# PowerInjectionControlBoardV4.net
KiCad netlist of a schematic drawn in EAGLE
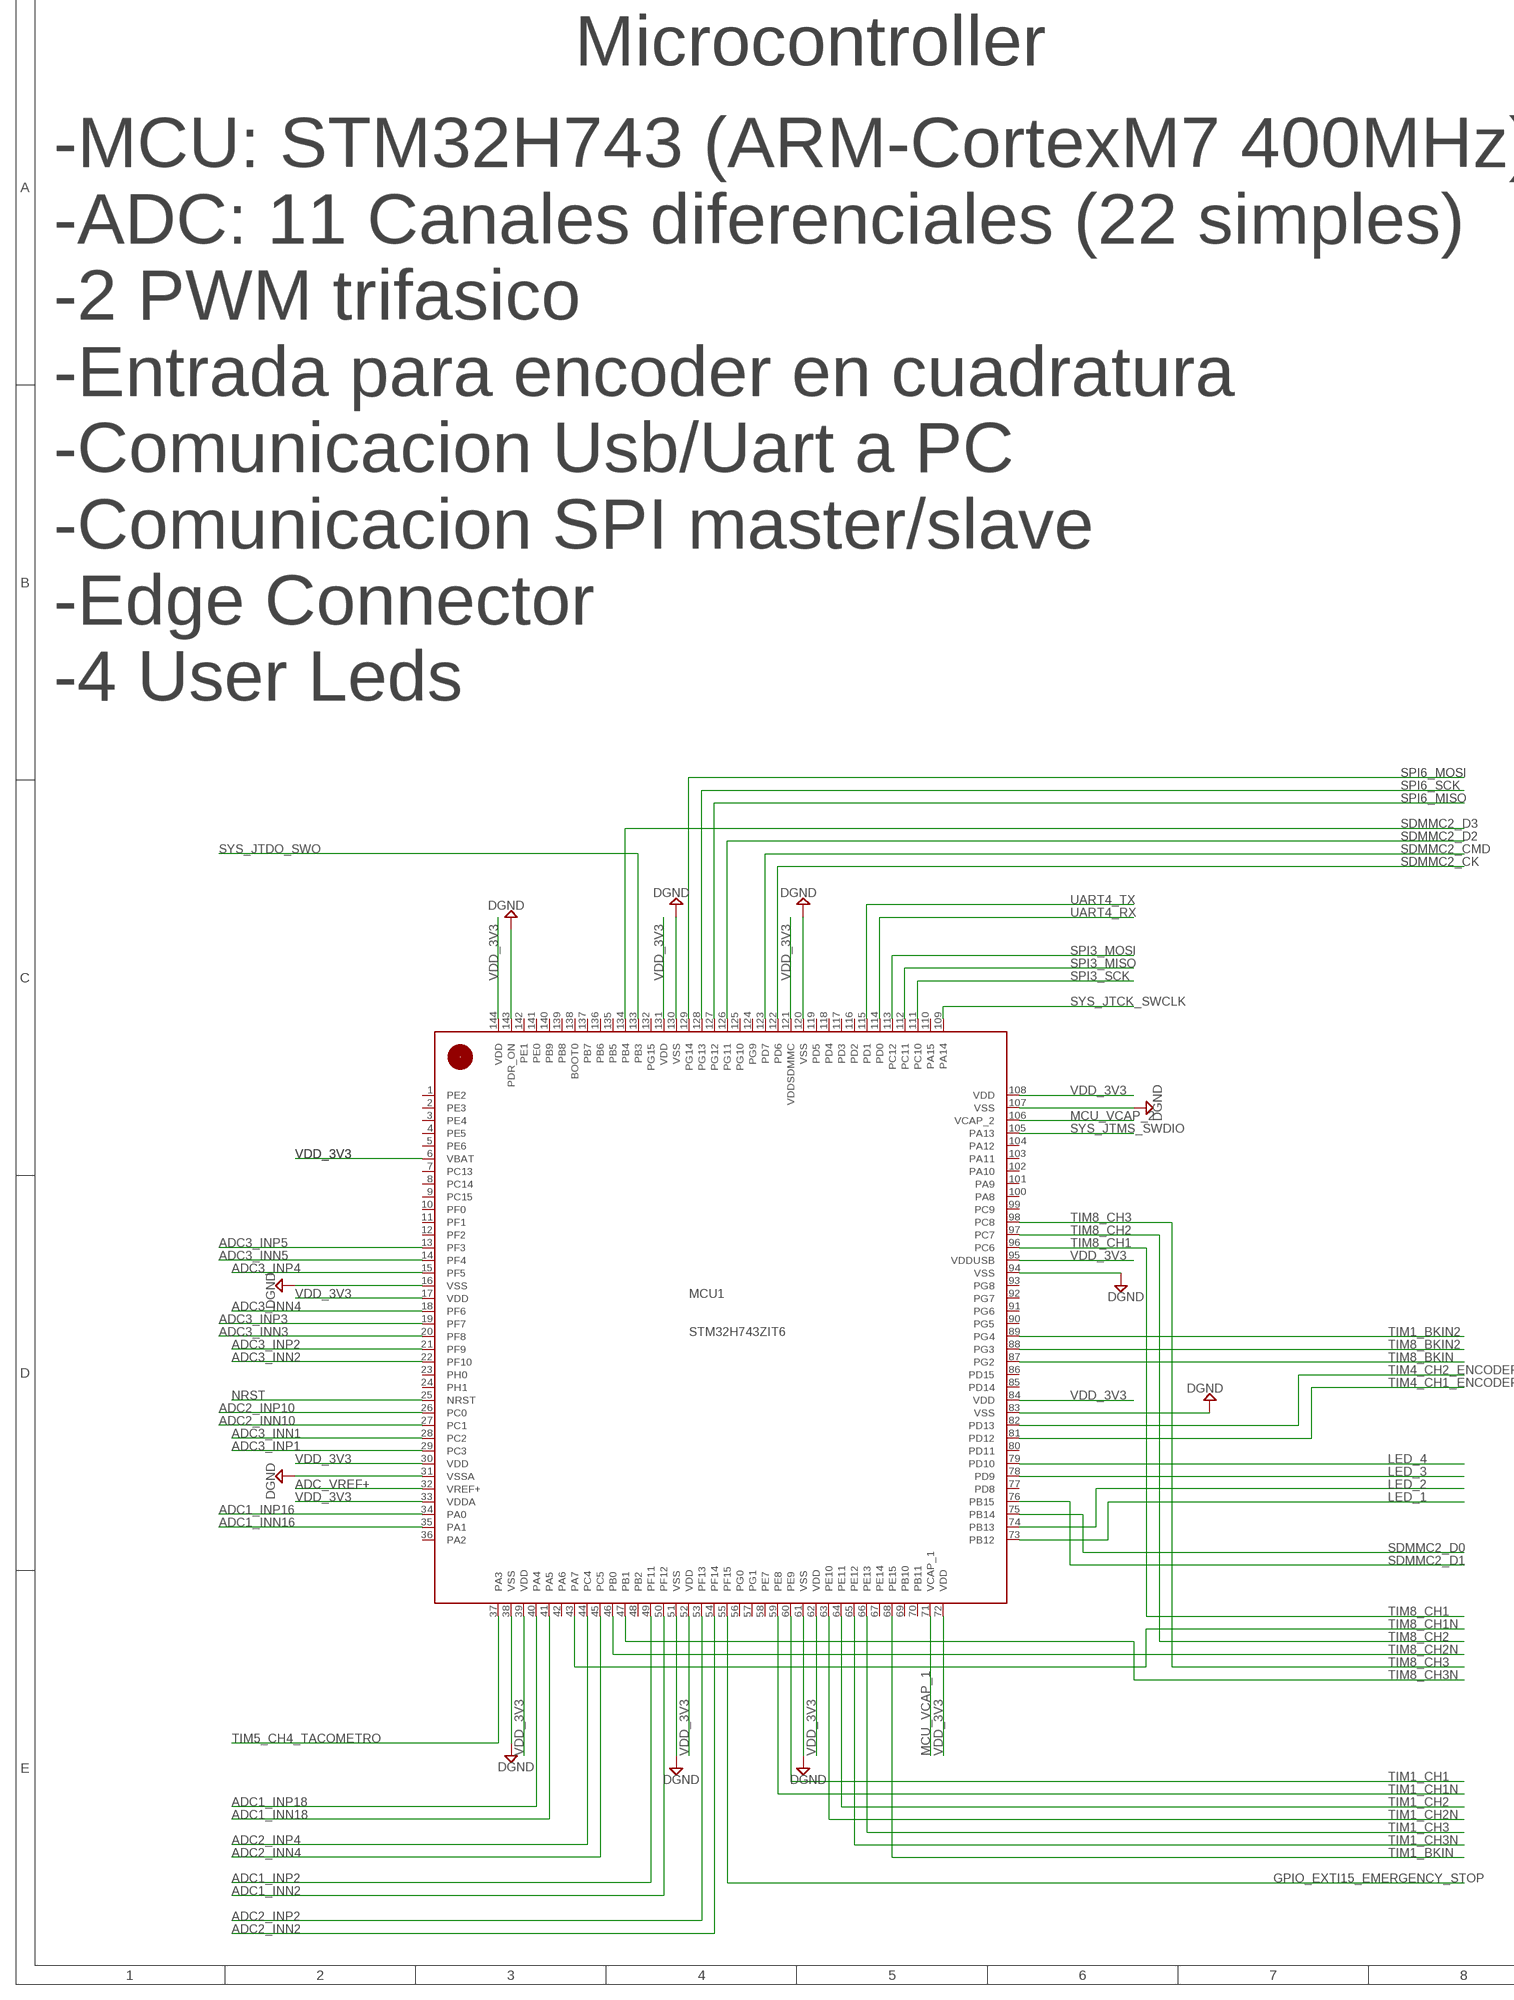
[diagram p0: schematic, sheet 1, part 1 of 2]
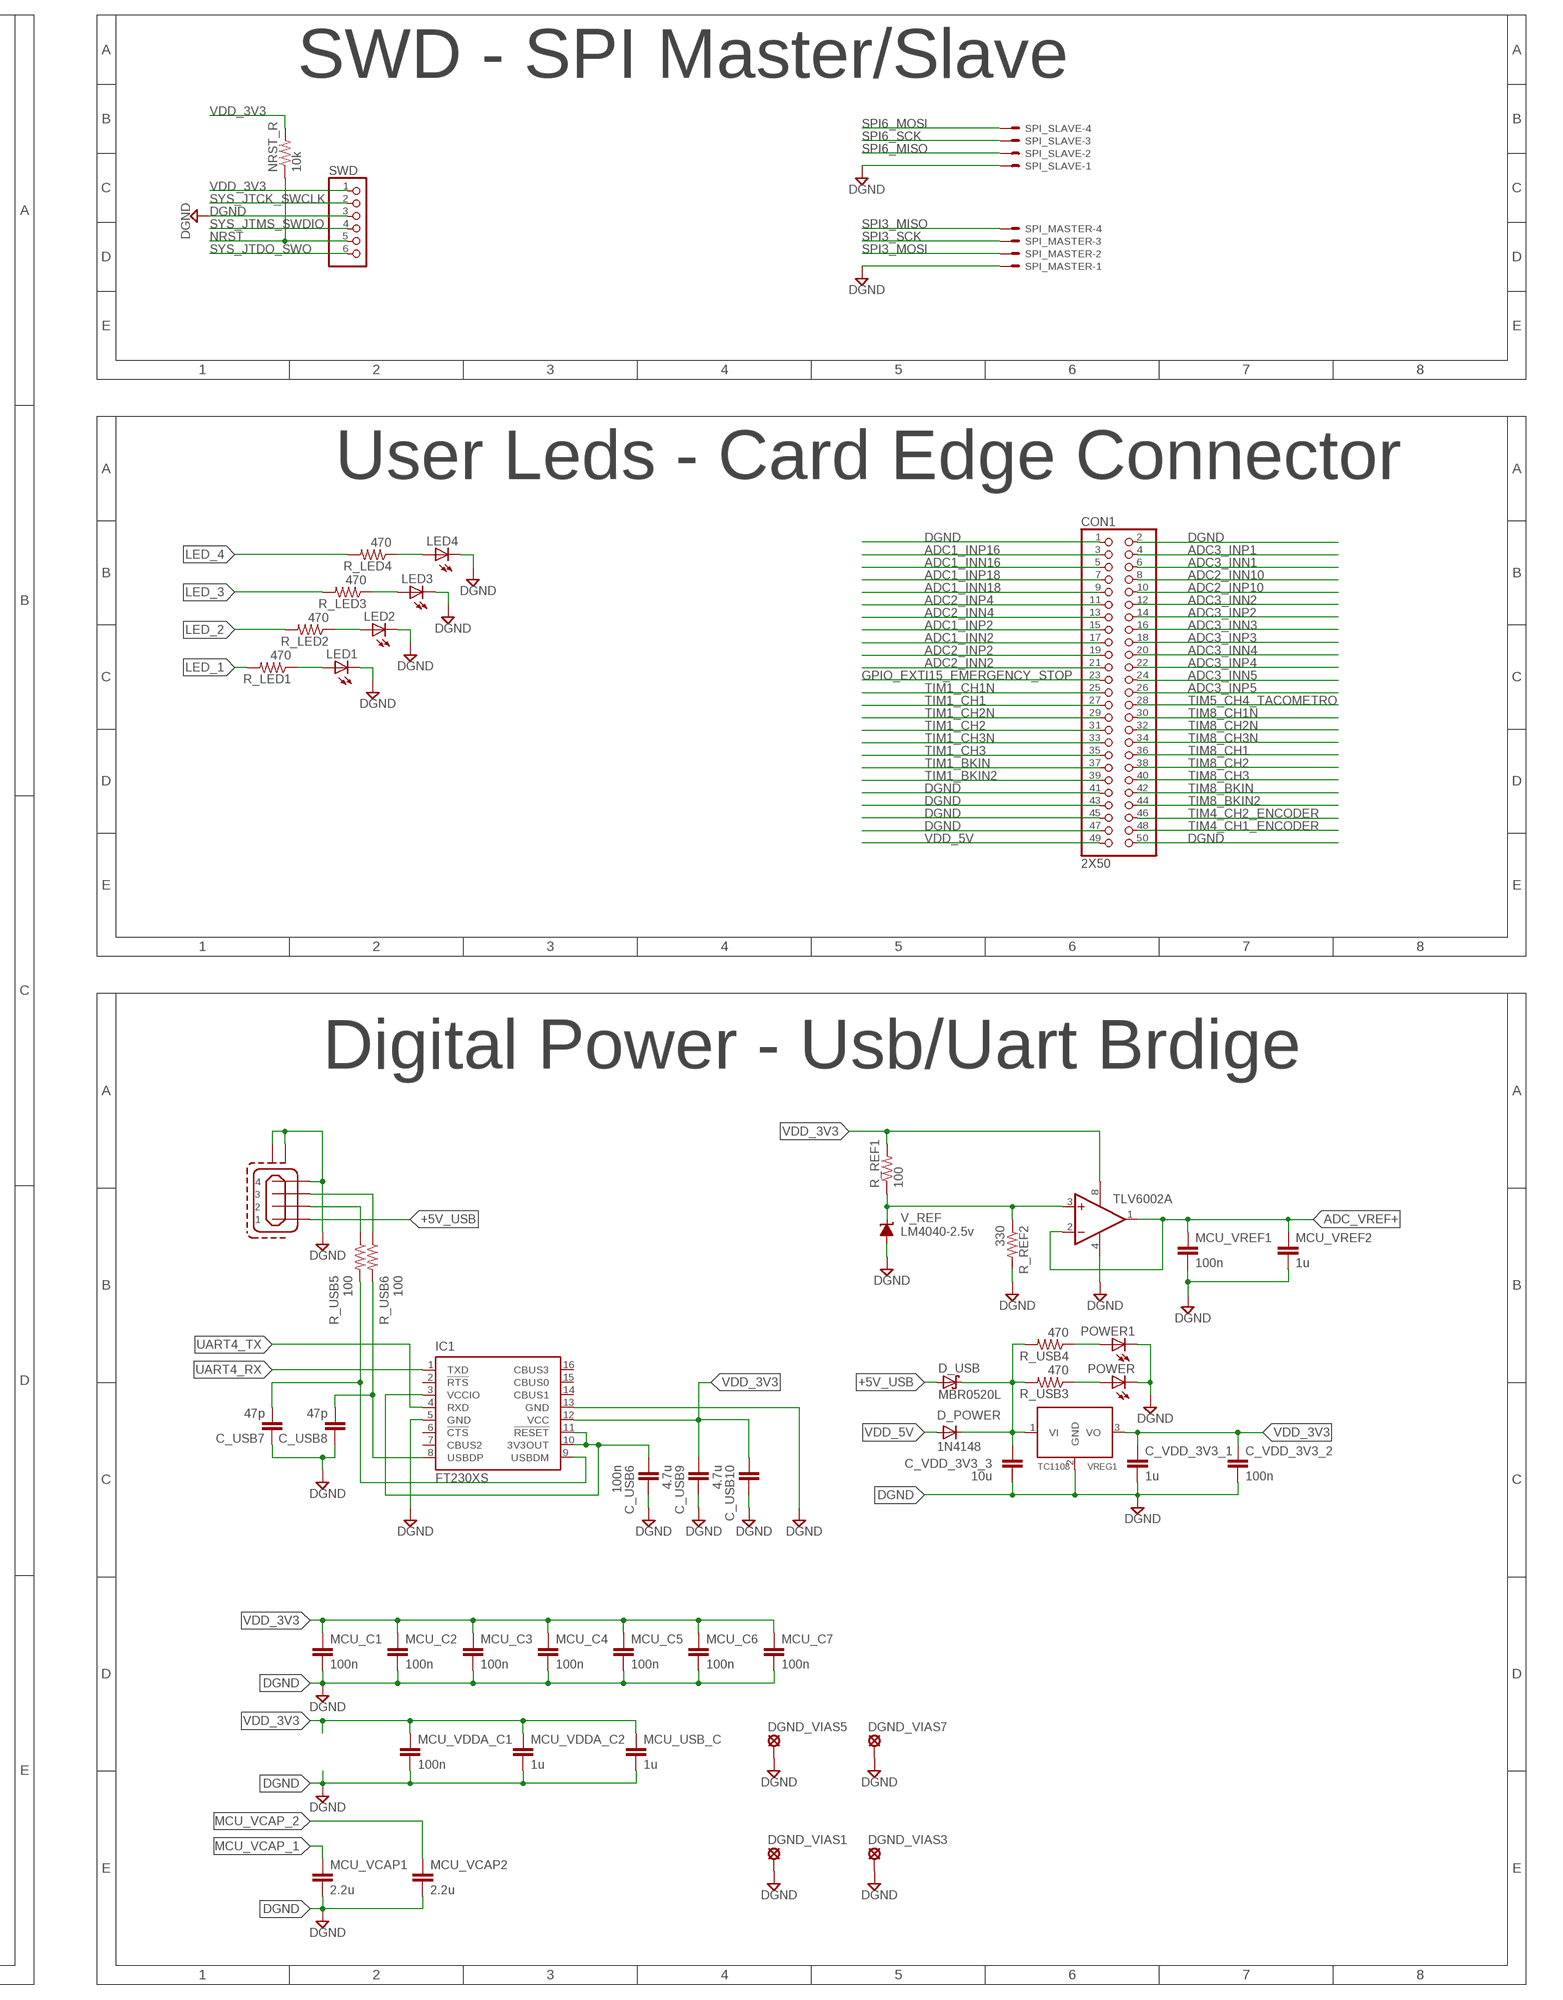
[diagram p1: schematic, sheet 1, part 2 of 2]

(export (version "E")
  (design (tool "Eeschema 10.0.6"))
  (components
    (comp (ref "CON1")
      (value "2X50")
      (footprint "eagle-import:2X25")
      (libsource (lib "eagle-import") (part "2X50"))
    )
    (comp (ref "C_USB6")
      (value "100n")
      (footprint "eagle-import:C0402")
      (libsource (lib "eagle-import") (part "C-EUC0402"))
    )
    (comp (ref "C_USB7")
      (value "47p")
      (footprint "eagle-import:C0402")
      (libsource (lib "eagle-import") (part "C-EUC0402"))
    )
    (comp (ref "C_USB8")
      (value "47p")
      (footprint "eagle-import:C0402")
      (libsource (lib "eagle-import") (part "C-EUC0402"))
    )
    (comp (ref "C_USB9")
      (value "4.7u")
      (footprint "eagle-import:C0402")
      (libsource (lib "eagle-import") (part "C-EUC0402"))
    )
    (comp (ref "C_USB10")
      (value "4.7u")
      (footprint "eagle-import:C0402")
      (libsource (lib "eagle-import") (part "C-EUC0402"))
    )
    (comp (ref "C_VDD_3V3_1")
      (value "1u")
      (footprint "eagle-import:C0603K")
      (libsource (lib "eagle-import") (part "C-EUC0603K"))
    )
    (comp (ref "C_VDD_3V3_2")
      (value "100n")
      (footprint "eagle-import:C0603K")
      (libsource (lib "eagle-import") (part "C-EUC0603K"))
    )
    (comp (ref "C_VDD_3V3_3")
      (value "10u")
      (footprint "eagle-import:C0603K")
      (libsource (lib "eagle-import") (part "C-EUC0603K"))
    )
    (comp (ref "DGND_VIAS1")
      (value "LSP10")
      (footprint "eagle-import:LSP10")
      (libsource (lib "eagle-import") (part "LSP10"))
    )
    (comp (ref "DGND_VIAS3")
      (value "LSP10")
      (footprint "eagle-import:LSP10")
      (libsource (lib "eagle-import") (part "LSP10"))
    )
    (comp (ref "DGND_VIAS5")
      (value "LSP10")
      (footprint "eagle-import:LSP10")
      (libsource (lib "eagle-import") (part "LSP10"))
    )
    (comp (ref "DGND_VIAS7")
      (value "LSP10")
      (footprint "eagle-import:LSP10")
      (libsource (lib "eagle-import") (part "LSP10"))
    )
    (comp (ref "D_POWER")
      (value "1N4148")
      (footprint "eagle-import:SMA-DO214AC")
      (libsource (lib "eagle-import") (part "GF1"))
    )
    (comp (ref "D_USB")
      (value "MBR0520L")
      (footprint "eagle-import:SOD-123")
      (libsource (lib "eagle-import") (part "MBR0520L"))
    )
    (comp (ref "IC1")
      (value "FT230XS")
      (footprint "eagle-import:SSOP16")
      (libsource (lib "eagle-import") (part "FT230XS"))
    )
    (comp (ref "LED1")
      (value "LEDCHIPLED_0805")
      (footprint "eagle-import:CHIPLED_0805")
      (libsource (lib "eagle-import") (part "LEDCHIPLED_0805"))
    )
    (comp (ref "LED2")
      (value "LEDCHIPLED_0805")
      (footprint "eagle-import:CHIPLED_0805")
      (libsource (lib "eagle-import") (part "LEDCHIPLED_0805"))
    )
    (comp (ref "LED3")
      (value "LEDCHIPLED_0805")
      (footprint "eagle-import:CHIPLED_0805")
      (libsource (lib "eagle-import") (part "LEDCHIPLED_0805"))
    )
    (comp (ref "LED4")
      (value "LEDCHIPLED_0805")
      (footprint "eagle-import:CHIPLED_0805")
      (libsource (lib "eagle-import") (part "LEDCHIPLED_0805"))
    )
    (comp (ref "MCU1")
      (value "STM32H743ZIT6'144'")
      (footprint "eagle-import:LQFP144")
      (libsource (lib "eagle-import") (part "STM32H743ZIT6'144'"))
    )
    (comp (ref "MCU_C1")
      (value "100n")
      (footprint "eagle-import:C0402")
      (libsource (lib "eagle-import") (part "C-EUC0402"))
    )
    (comp (ref "MCU_C2")
      (value "100n")
      (footprint "eagle-import:C0402")
      (libsource (lib "eagle-import") (part "C-EUC0402"))
    )
    (comp (ref "MCU_C3")
      (value "100n")
      (footprint "eagle-import:C0402")
      (libsource (lib "eagle-import") (part "C-EUC0402"))
    )
    (comp (ref "MCU_C4")
      (value "100n")
      (footprint "eagle-import:C0402")
      (libsource (lib "eagle-import") (part "C-EUC0402"))
    )
    (comp (ref "MCU_C5")
      (value "100n")
      (footprint "eagle-import:C0402")
      (libsource (lib "eagle-import") (part "C-EUC0402"))
    )
    (comp (ref "MCU_C6")
      (value "100n")
      (footprint "eagle-import:C0402")
      (libsource (lib "eagle-import") (part "C-EUC0402"))
    )
    (comp (ref "MCU_C7")
      (value "100n")
      (footprint "eagle-import:C0402")
      (libsource (lib "eagle-import") (part "C-EUC0402"))
    )
    (comp (ref "MCU_USB_C")
      (value "1u")
      (footprint "eagle-import:C0402")
      (libsource (lib "eagle-import") (part "C-EUC0402"))
    )
    (comp (ref "MCU_VCAP1")
      (value "2.2u")
      (footprint "eagle-import:C0402")
      (libsource (lib "eagle-import") (part "C-EUC0402"))
    )
    (comp (ref "MCU_VCAP2")
      (value "2.2u")
      (footprint "eagle-import:C0402")
      (libsource (lib "eagle-import") (part "C-EUC0402"))
    )
    (comp (ref "MCU_VDDA_C1")
      (value "100n")
      (footprint "eagle-import:C0402")
      (libsource (lib "eagle-import") (part "C-EUC0402"))
    )
    (comp (ref "MCU_VDDA_C2")
      (value "1u")
      (footprint "eagle-import:C0402")
      (libsource (lib "eagle-import") (part "C-EUC0402"))
    )
    (comp (ref "MCU_VREF1")
      (value "100n")
      (footprint "eagle-import:C0402")
      (libsource (lib "eagle-import") (part "C-EUC0402"))
    )
    (comp (ref "MCU_VREF2")
      (value "1u")
      (footprint "eagle-import:C0402")
      (libsource (lib "eagle-import") (part "C-EUC0402"))
    )
    (comp (ref "NRST_R")
      (value "10k")
      (footprint "eagle-import:R0402")
      (libsource (lib "eagle-import") (part "R-US_R0402"))
    )
    (comp (ref "POWER")
      (value "LEDCHIPLED_0805")
      (footprint "eagle-import:CHIPLED_0805")
      (libsource (lib "eagle-import") (part "LEDCHIPLED_0805"))
    )
    (comp (ref "POWER1")
      (value "LEDCHIPLED_0805")
      (footprint "eagle-import:CHIPLED_0805")
      (libsource (lib "eagle-import") (part "LEDCHIPLED_0805"))
    )
    (comp (ref "R_LED1")
      (value "470")
      (footprint "eagle-import:R0402")
      (libsource (lib "eagle-import") (part "R-US_R0402"))
    )
    (comp (ref "R_LED2")
      (value "470")
      (footprint "eagle-import:R0402")
      (libsource (lib "eagle-import") (part "R-US_R0402"))
    )
    (comp (ref "R_LED3")
      (value "470")
      (footprint "eagle-import:R0402")
      (libsource (lib "eagle-import") (part "R-US_R0402"))
    )
    (comp (ref "R_LED4")
      (value "470")
      (footprint "eagle-import:R0402")
      (libsource (lib "eagle-import") (part "R-US_R0402"))
    )
    (comp (ref "R_REF1")
      (value "100")
      (footprint "eagle-import:R0805")
      (libsource (lib "eagle-import") (part "R-US_R0805"))
    )
    (comp (ref "R_REF2")
      (value "330")
      (footprint "eagle-import:R0805")
      (libsource (lib "eagle-import") (part "R-US_R0805"))
    )
    (comp (ref "R_USB3")
      (value "470")
      (footprint "eagle-import:R0402")
      (libsource (lib "eagle-import") (part "R-US_R0402"))
    )
    (comp (ref "R_USB4")
      (value "470")
      (footprint "eagle-import:R0402")
      (libsource (lib "eagle-import") (part "R-US_R0402"))
    )
    (comp (ref "R_USB5")
      (value "100")
      (footprint "eagle-import:R0402")
      (libsource (lib "eagle-import") (part "R-US_R0402"))
    )
    (comp (ref "R_USB6")
      (value "100")
      (footprint "eagle-import:R0402")
      (libsource (lib "eagle-import") (part "R-US_R0402"))
    )
    (comp (ref "SPI_MASTER")
      (value "22-23-2041")
      (footprint "eagle-import:22-23-2041")
      (fields (field (name "MF") "MOLEX"))
      (libsource (lib "eagle-import") (part "22-23-2041"))
    )
    (comp (ref "SPI_SLAVE")
      (value "22-23-2041")
      (footprint "eagle-import:22-23-2041")
      (fields (field (name "MF") "MOLEX"))
      (libsource (lib "eagle-import") (part "22-23-2041"))
    )
    (comp (ref "SWD")
      (value "PINHD-1X6/90")
      (footprint "eagle-import:1X06_90")
      (libsource (lib "eagle-import") (part "PINHD-1X6/90"))
    )
    (comp (ref "TLV6002")
      (value "TL082D")
      (footprint "eagle-import:SO08")
      (libsource (lib "eagle-import") (part "TL082D"))
    )
    (comp (ref "VREG1")
      (value "TC1108'SOT-223'")
      (footprint "eagle-import:SOT-223")
      (libsource (lib "eagle-import") (part "TC1108'SOT-223'"))
    )
    (comp (ref "V_REF")
      (value "LM4040-2.5v")
      (footprint "eagle-import:DBZ_R-PDSO-G3")
      (fields (field (name "MPN") "LM4041A12IDBZR"))
      (libsource (lib "eagle-import") (part "LM4041DBZA12"))
    )
    (comp (ref "X2")
      (value "MINI-USB_SHIELD4P-85-32004-00X")
      (footprint "eagle-import:85-32004-00X")
      (libsource (lib "eagle-import") (part "MINI-USB_SHIELD4P-85-32004-00X"))
    )
  )
  (nets
    (net (code "1") (name "+5V_USB") (class "Default")
      (node (ref "D_USB") (pin "A") (pinfunction "IN_A") (pintype "passive"))
      (node (ref "X2") (pin "1") (pinfunction "1_1") (pintype "passive"))
    )
    (net (code "2") (name "/ADC1_INN2") (class "Default")
      (node (ref "CON1") (pin "17") (pinfunction "17_17") (pintype "passive"))
      (node (ref "MCU1") (pin "50") (pinfunction "PF12_50") (pintype "bidirectional"))
    )
    (net (code "3") (name "/ADC1_INN16") (class "Default")
      (node (ref "CON1") (pin "5") (pinfunction "5_5") (pintype "passive"))
      (node (ref "MCU1") (pin "35") (pinfunction "PA1_35") (pintype "bidirectional"))
    )
    (net (code "4") (name "/ADC1_INN18") (class "Default")
      (node (ref "CON1") (pin "9") (pinfunction "9_9") (pintype "passive"))
      (node (ref "MCU1") (pin "41") (pinfunction "PA5_41") (pintype "bidirectional"))
    )
    (net (code "5") (name "/ADC1_INP2") (class "Default")
      (node (ref "CON1") (pin "15") (pinfunction "15_15") (pintype "passive"))
      (node (ref "MCU1") (pin "49") (pinfunction "PF11_49") (pintype "bidirectional"))
    )
    (net (code "6") (name "/ADC1_INP16") (class "Default")
      (node (ref "CON1") (pin "3") (pinfunction "3_3") (pintype "passive"))
      (node (ref "MCU1") (pin "34") (pinfunction "PA0_34") (pintype "bidirectional"))
    )
    (net (code "7") (name "/ADC1_INP18") (class "Default")
      (node (ref "CON1") (pin "7") (pinfunction "7_7") (pintype "passive"))
      (node (ref "MCU1") (pin "40") (pinfunction "PA4_40") (pintype "bidirectional"))
    )
    (net (code "8") (name "/ADC2_INN2") (class "Default")
      (node (ref "CON1") (pin "21") (pinfunction "21_21") (pintype "passive"))
      (node (ref "MCU1") (pin "54") (pinfunction "PF14_54") (pintype "bidirectional"))
    )
    (net (code "9") (name "/ADC2_INN4") (class "Default")
      (node (ref "CON1") (pin "13") (pinfunction "13_13") (pintype "passive"))
      (node (ref "MCU1") (pin "45") (pinfunction "PC5_45") (pintype "bidirectional"))
    )
    (net (code "10") (name "/ADC2_INN10") (class "Default")
      (node (ref "CON1") (pin "8") (pinfunction "8_8") (pintype "passive"))
      (node (ref "MCU1") (pin "27") (pinfunction "PC1_27") (pintype "bidirectional"))
    )
    (net (code "11") (name "/ADC2_INP2") (class "Default")
      (node (ref "CON1") (pin "19") (pinfunction "19_19") (pintype "passive"))
      (node (ref "MCU1") (pin "53") (pinfunction "PF13_53") (pintype "bidirectional"))
    )
    (net (code "12") (name "/ADC2_INP4") (class "Default")
      (node (ref "CON1") (pin "11") (pinfunction "11_11") (pintype "passive"))
      (node (ref "MCU1") (pin "44") (pinfunction "PC4_44") (pintype "bidirectional"))
    )
    (net (code "13") (name "/ADC2_INP10") (class "Default")
      (node (ref "CON1") (pin "10") (pinfunction "10_10") (pintype "passive"))
      (node (ref "MCU1") (pin "26") (pinfunction "PC0_26") (pintype "bidirectional"))
    )
    (net (code "14") (name "/ADC3_INN1") (class "Default")
      (node (ref "CON1") (pin "6") (pinfunction "6_6") (pintype "passive"))
      (node (ref "MCU1") (pin "28") (pinfunction "PC2_28") (pintype "bidirectional"))
    )
    (net (code "15") (name "/ADC3_INN2") (class "Default")
      (node (ref "CON1") (pin "12") (pinfunction "12_12") (pintype "passive"))
      (node (ref "MCU1") (pin "22") (pinfunction "PF10_22") (pintype "bidirectional"))
    )
    (net (code "16") (name "/ADC3_INN3") (class "Default")
      (node (ref "CON1") (pin "16") (pinfunction "16_16") (pintype "passive"))
      (node (ref "MCU1") (pin "20") (pinfunction "PF8_20") (pintype "bidirectional"))
    )
    (net (code "17") (name "/ADC3_INN4") (class "Default")
      (node (ref "CON1") (pin "20") (pinfunction "20_20") (pintype "passive"))
      (node (ref "MCU1") (pin "18") (pinfunction "PF6_18") (pintype "bidirectional"))
    )
    (net (code "18") (name "/ADC3_INN5") (class "Default")
      (node (ref "CON1") (pin "24") (pinfunction "24_24") (pintype "passive"))
      (node (ref "MCU1") (pin "14") (pinfunction "PF4_14") (pintype "bidirectional"))
    )
    (net (code "19") (name "/ADC3_INP1") (class "Default")
      (node (ref "CON1") (pin "4") (pinfunction "4_4") (pintype "passive"))
      (node (ref "MCU1") (pin "29") (pinfunction "PC3_29") (pintype "bidirectional"))
    )
    (net (code "20") (name "/ADC3_INP2") (class "Default")
      (node (ref "CON1") (pin "14") (pinfunction "14_14") (pintype "passive"))
      (node (ref "MCU1") (pin "21") (pinfunction "PF9_21") (pintype "bidirectional"))
    )
    (net (code "21") (name "/ADC3_INP3") (class "Default")
      (node (ref "CON1") (pin "18") (pinfunction "18_18") (pintype "passive"))
      (node (ref "MCU1") (pin "19") (pinfunction "PF7_19") (pintype "bidirectional"))
    )
    (net (code "22") (name "/ADC3_INP4") (class "Default")
      (node (ref "CON1") (pin "22") (pinfunction "22_22") (pintype "passive"))
      (node (ref "MCU1") (pin "15") (pinfunction "PF5_15") (pintype "bidirectional"))
    )
    (net (code "23") (name "/ADC3_INP5") (class "Default")
      (node (ref "CON1") (pin "26") (pinfunction "26_26") (pintype "passive"))
      (node (ref "MCU1") (pin "13") (pinfunction "PF3_13") (pintype "bidirectional"))
    )
    (net (code "24") (name "/GPIO_EXTI15_EMERGENCY_STOP") (class "Default")
      (node (ref "CON1") (pin "23") (pinfunction "23_23") (pintype "passive"))
      (node (ref "MCU1") (pin "55") (pinfunction "PF15_55") (pintype "bidirectional"))
    )
    (net (code "25") (name "/NRST") (class "Default")
      (node (ref "MCU1") (pin "25") (pinfunction "NRST_25") (pintype "bidirectional"))
      (node (ref "NRST_R") (pin "1") (pinfunction "1_1") (pintype "passive"))
      (node (ref "SWD") (pin "5") (pinfunction "5_5") (pintype "passive"))
    )
    (net (code "26") (name "/SDMMC2_CK") (class "Default")
      (node (ref "MCU1") (pin "122") (pinfunction "PD6_122") (pintype "bidirectional"))
    )
    (net (code "27") (name "/SDMMC2_CMD") (class "Default")
      (node (ref "MCU1") (pin "123") (pinfunction "PD7_123") (pintype "bidirectional"))
    )
    (net (code "28") (name "/SDMMC2_D0") (class "Default")
      (node (ref "MCU1") (pin "75") (pinfunction "PB14_75") (pintype "bidirectional"))
    )
    (net (code "29") (name "/SDMMC2_D1") (class "Default")
      (node (ref "MCU1") (pin "76") (pinfunction "PB15_76") (pintype "bidirectional"))
    )
    (net (code "30") (name "/SDMMC2_D2") (class "Default")
      (node (ref "MCU1") (pin "126") (pinfunction "PG11_126") (pintype "bidirectional"))
    )
    (net (code "31") (name "/SDMMC2_D3") (class "Default")
      (node (ref "MCU1") (pin "134") (pinfunction "PB4_134") (pintype "bidirectional"))
    )
    (net (code "32") (name "/SPI3_MISO") (class "Default")
      (node (ref "MCU1") (pin "112") (pinfunction "PC11_112") (pintype "bidirectional"))
      (node (ref "SPI_MASTER") (pin "4") (pinfunction "S_4") (pintype "passive"))
    )
    (net (code "33") (name "/SPI3_MOSI") (class "Default")
      (node (ref "MCU1") (pin "113") (pinfunction "PC12_113") (pintype "bidirectional"))
      (node (ref "SPI_MASTER") (pin "2") (pinfunction "S_2") (pintype "passive"))
    )
    (net (code "34") (name "/SPI3_SCK") (class "Default")
      (node (ref "MCU1") (pin "111") (pinfunction "PC10_111") (pintype "bidirectional"))
      (node (ref "SPI_MASTER") (pin "3") (pinfunction "S_3") (pintype "passive"))
    )
    (net (code "35") (name "/SPI6_MISO") (class "Default")
      (node (ref "MCU1") (pin "127") (pinfunction "PG12_127") (pintype "bidirectional"))
      (node (ref "SPI_SLAVE") (pin "2") (pinfunction "S_2") (pintype "passive"))
    )
    (net (code "36") (name "/SPI6_MOSI") (class "Default")
      (node (ref "MCU1") (pin "129") (pinfunction "PG14_129") (pintype "bidirectional"))
      (node (ref "SPI_SLAVE") (pin "4") (pinfunction "S_4") (pintype "passive"))
    )
    (net (code "37") (name "/SPI6_SCK") (class "Default")
      (node (ref "MCU1") (pin "128") (pinfunction "PG13_128") (pintype "bidirectional"))
      (node (ref "SPI_SLAVE") (pin "3") (pinfunction "S_3") (pintype "passive"))
    )
    (net (code "38") (name "/SYS_JTCK_SWCLK") (class "Default")
      (node (ref "MCU1") (pin "109") (pinfunction "PA14_109") (pintype "bidirectional"))
      (node (ref "SWD") (pin "2") (pinfunction "2_2") (pintype "passive"))
    )
    (net (code "39") (name "/SYS_JTDO_SWO") (class "Default")
      (node (ref "MCU1") (pin "133") (pinfunction "PB3_133") (pintype "bidirectional"))
      (node (ref "SWD") (pin "6") (pinfunction "6_6") (pintype "passive"))
    )
    (net (code "40") (name "/SYS_JTMS_SWDIO") (class "Default")
      (node (ref "MCU1") (pin "105") (pinfunction "PA13_105") (pintype "bidirectional"))
      (node (ref "SWD") (pin "4") (pinfunction "4_4") (pintype "passive"))
    )
    (net (code "41") (name "/TIM1_BKIN") (class "Default")
      (node (ref "CON1") (pin "37") (pinfunction "37_37") (pintype "passive"))
      (node (ref "MCU1") (pin "68") (pinfunction "PE15_68") (pintype "bidirectional"))
    )
    (net (code "42") (name "/TIM1_BKIN2") (class "Default")
      (node (ref "CON1") (pin "39") (pinfunction "39_39") (pintype "passive"))
      (node (ref "MCU1") (pin "89") (pinfunction "PG4_89") (pintype "bidirectional"))
    )
    (net (code "43") (name "/TIM1_CH1") (class "Default")
      (node (ref "CON1") (pin "27") (pinfunction "27_27") (pintype "passive"))
      (node (ref "MCU1") (pin "60") (pinfunction "PE9_60") (pintype "bidirectional"))
    )
    (net (code "44") (name "/TIM1_CH1N") (class "Default")
      (node (ref "CON1") (pin "25") (pinfunction "25_25") (pintype "passive"))
      (node (ref "MCU1") (pin "59") (pinfunction "PE8_59") (pintype "bidirectional"))
    )
    (net (code "45") (name "/TIM1_CH2") (class "Default")
      (node (ref "CON1") (pin "31") (pinfunction "31_31") (pintype "passive"))
      (node (ref "MCU1") (pin "64") (pinfunction "PE11_64") (pintype "bidirectional"))
    )
    (net (code "46") (name "/TIM1_CH2N") (class "Default")
      (node (ref "CON1") (pin "29") (pinfunction "29_29") (pintype "passive"))
      (node (ref "MCU1") (pin "63") (pinfunction "PE10_63") (pintype "bidirectional"))
    )
    (net (code "47") (name "/TIM1_CH3") (class "Default")
      (node (ref "CON1") (pin "35") (pinfunction "35_35") (pintype "passive"))
      (node (ref "MCU1") (pin "66") (pinfunction "PE13_66") (pintype "bidirectional"))
    )
    (net (code "48") (name "/TIM1_CH3N") (class "Default")
      (node (ref "CON1") (pin "33") (pinfunction "33_33") (pintype "passive"))
      (node (ref "MCU1") (pin "65") (pinfunction "PE12_65") (pintype "bidirectional"))
    )
    (net (code "49") (name "/TIM4_CH1_ENCODER") (class "Default")
      (node (ref "CON1") (pin "48") (pinfunction "48_48") (pintype "passive"))
      (node (ref "MCU1") (pin "81") (pinfunction "PD12_81") (pintype "bidirectional"))
    )
    (net (code "50") (name "/TIM4_CH2_ENCODER") (class "Default")
      (node (ref "CON1") (pin "46") (pinfunction "46_46") (pintype "passive"))
      (node (ref "MCU1") (pin "82") (pinfunction "PD13_82") (pintype "bidirectional"))
    )
    (net (code "51") (name "/TIM5_CH4_TACOMETRO") (class "Default")
      (node (ref "CON1") (pin "28") (pinfunction "28_28") (pintype "passive"))
      (node (ref "MCU1") (pin "37") (pinfunction "PA3_37") (pintype "bidirectional"))
    )
    (net (code "52") (name "/TIM8_BKIN") (class "Default")
      (node (ref "CON1") (pin "42") (pinfunction "42_42") (pintype "passive"))
      (node (ref "MCU1") (pin "87") (pinfunction "PG2_87") (pintype "bidirectional"))
    )
    (net (code "53") (name "/TIM8_BKIN2") (class "Default")
      (node (ref "CON1") (pin "44") (pinfunction "44_44") (pintype "passive"))
      (node (ref "MCU1") (pin "88") (pinfunction "PG3_88") (pintype "bidirectional"))
    )
    (net (code "54") (name "/TIM8_CH1") (class "Default")
      (node (ref "CON1") (pin "36") (pinfunction "36_36") (pintype "passive"))
      (node (ref "MCU1") (pin "96") (pinfunction "PC6_96") (pintype "bidirectional"))
    )
    (net (code "55") (name "/TIM8_CH1N") (class "Default")
      (node (ref "CON1") (pin "30") (pinfunction "30_30") (pintype "passive"))
      (node (ref "MCU1") (pin "43") (pinfunction "PA7_43") (pintype "bidirectional"))
    )
    (net (code "56") (name "/TIM8_CH2") (class "Default")
      (node (ref "CON1") (pin "38") (pinfunction "38_38") (pintype "passive"))
      (node (ref "MCU1") (pin "97") (pinfunction "PC7_97") (pintype "bidirectional"))
    )
    (net (code "57") (name "/TIM8_CH2N") (class "Default")
      (node (ref "CON1") (pin "32") (pinfunction "32_32") (pintype "passive"))
      (node (ref "MCU1") (pin "46") (pinfunction "PB0_46") (pintype "bidirectional"))
    )
    (net (code "58") (name "/TIM8_CH3") (class "Default")
      (node (ref "CON1") (pin "40") (pinfunction "40_40") (pintype "passive"))
      (node (ref "MCU1") (pin "98") (pinfunction "PC8_98") (pintype "bidirectional"))
    )
    (net (code "59") (name "/TIM8_CH3N") (class "Default")
      (node (ref "CON1") (pin "34") (pinfunction "34_34") (pintype "passive"))
      (node (ref "MCU1") (pin "47") (pinfunction "PB1_47") (pintype "bidirectional"))
    )
    (net (code "60") (name "ADC_VREF+") (class "Default")
      (node (ref "MCU1") (pin "32") (pinfunction "VREF+_32") (pintype "bidirectional"))
      (node (ref "MCU_VREF1") (pin "1") (pinfunction "1_1") (pintype "passive"))
      (node (ref "MCU_VREF2") (pin "1") (pinfunction "1_1") (pintype "passive"))
      (node (ref "TLV6002") (pin "1") (pinfunction "OUT_1") (pintype "output"))
      (node (ref "TLV6002") (pin "2") (pinfunction "-IN_2") (pintype "input"))
    )
    (net (code "61") (name "DGND") (class "Default")
      (node (ref "CON1") (pin "1") (pinfunction "1_1") (pintype "passive"))
      (node (ref "CON1") (pin "2") (pinfunction "2_2") (pintype "passive"))
      (node (ref "CON1") (pin "41") (pinfunction "41_41") (pintype "passive"))
      (node (ref "CON1") (pin "43") (pinfunction "43_43") (pintype "passive"))
      (node (ref "CON1") (pin "45") (pinfunction "45_45") (pintype "passive"))
      (node (ref "CON1") (pin "47") (pinfunction "47_47") (pintype "passive"))
      (node (ref "CON1") (pin "50") (pinfunction "50_50") (pintype "passive"))
      (node (ref "C_USB10") (pin "1") (pinfunction "1_1") (pintype "passive"))
      (node (ref "C_USB6") (pin "1") (pinfunction "1_1") (pintype "passive"))
      (node (ref "C_USB7") (pin "1") (pinfunction "1_1") (pintype "passive"))
      (node (ref "C_USB8") (pin "1") (pinfunction "1_1") (pintype "passive"))
      (node (ref "C_USB9") (pin "1") (pinfunction "1_1") (pintype "passive"))
      (node (ref "C_VDD_3V3_1") (pin "2") (pinfunction "2_2") (pintype "passive"))
      (node (ref "C_VDD_3V3_2") (pin "2") (pinfunction "2_2") (pintype "passive"))
      (node (ref "C_VDD_3V3_3") (pin "2") (pinfunction "2_2") (pintype "passive"))
      (node (ref "DGND_VIAS1") (pin "MP") (pinfunction "MP_MP") (pintype "passive"))
      (node (ref "DGND_VIAS3") (pin "MP") (pinfunction "MP_MP") (pintype "passive"))
      (node (ref "DGND_VIAS5") (pin "MP") (pinfunction "MP_MP") (pintype "passive"))
      (node (ref "DGND_VIAS7") (pin "MP") (pinfunction "MP_MP") (pintype "passive"))
      (node (ref "IC1") (pin "13") (pinfunction "GND_13") (pintype "power_in"))
      (node (ref "IC1") (pin "5") (pinfunction "GND_5") (pintype "power_in"))
      (node (ref "LED1") (pin "C") (pinfunction "C_C") (pintype "passive"))
      (node (ref "LED2") (pin "C") (pinfunction "C_C") (pintype "passive"))
      (node (ref "LED3") (pin "C") (pinfunction "C_C") (pintype "passive"))
      (node (ref "LED4") (pin "C") (pinfunction "C_C") (pintype "passive"))
      (node (ref "MCU1") (pin "107") (pinfunction "VSS_107") (pintype "bidirectional"))
      (node (ref "MCU1") (pin "120") (pinfunction "VSS_120") (pintype "bidirectional"))
      (node (ref "MCU1") (pin "130") (pinfunction "VSS_130") (pintype "bidirectional"))
      (node (ref "MCU1") (pin "143") (pinfunction "PDR_ON_143") (pintype "bidirectional"))
      (node (ref "MCU1") (pin "16") (pinfunction "VSS_16") (pintype "bidirectional"))
      (node (ref "MCU1") (pin "31") (pinfunction "VSSA_31") (pintype "bidirectional"))
      (node (ref "MCU1") (pin "38") (pinfunction "VSS_38") (pintype "bidirectional"))
      (node (ref "MCU1") (pin "51") (pinfunction "VSS_51") (pintype "bidirectional"))
      (node (ref "MCU1") (pin "61") (pinfunction "VSS_61") (pintype "bidirectional"))
      (node (ref "MCU1") (pin "83") (pinfunction "VSS_83") (pintype "bidirectional"))
      (node (ref "MCU1") (pin "94") (pinfunction "VSS_94") (pintype "bidirectional"))
      (node (ref "MCU_C1") (pin "2") (pinfunction "2_2") (pintype "passive"))
      (node (ref "MCU_C2") (pin "2") (pinfunction "2_2") (pintype "passive"))
      (node (ref "MCU_C3") (pin "2") (pinfunction "2_2") (pintype "passive"))
      (node (ref "MCU_C4") (pin "2") (pinfunction "2_2") (pintype "passive"))
      (node (ref "MCU_C5") (pin "2") (pinfunction "2_2") (pintype "passive"))
      (node (ref "MCU_C6") (pin "2") (pinfunction "2_2") (pintype "passive"))
      (node (ref "MCU_C7") (pin "2") (pinfunction "2_2") (pintype "passive"))
      (node (ref "MCU_USB_C") (pin "2") (pinfunction "2_2") (pintype "passive"))
      (node (ref "MCU_VCAP1") (pin "2") (pinfunction "2_2") (pintype "passive"))
      (node (ref "MCU_VCAP2") (pin "2") (pinfunction "2_2") (pintype "passive"))
      (node (ref "MCU_VDDA_C1") (pin "2") (pinfunction "2_2") (pintype "passive"))
      (node (ref "MCU_VDDA_C2") (pin "2") (pinfunction "2_2") (pintype "passive"))
      (node (ref "MCU_VREF1") (pin "2") (pinfunction "2_2") (pintype "passive"))
      (node (ref "MCU_VREF2") (pin "2") (pinfunction "2_2") (pintype "passive"))
      (node (ref "POWER") (pin "C") (pinfunction "C_C") (pintype "passive"))
      (node (ref "POWER1") (pin "C") (pinfunction "C_C") (pintype "passive"))
      (node (ref "R_REF2") (pin "2") (pinfunction "2_2") (pintype "passive"))
      (node (ref "SPI_MASTER") (pin "1") (pinfunction "S_1") (pintype "passive"))
      (node (ref "SPI_SLAVE") (pin "1") (pinfunction "S_1") (pintype "passive"))
      (node (ref "SWD") (pin "3") (pinfunction "3_3") (pintype "passive"))
      (node (ref "TLV6002") (pin "4") (pinfunction "V-_4") (pintype "power_in"))
      (node (ref "VREG1") (pin "2") (pinfunction "GND_2") (pintype "bidirectional"))
      (node (ref "V_REF") (pin "2") (pinfunction "A_2") (pintype "passive"))
      (node (ref "X2") (pin "4") (pinfunction "4_4") (pintype "passive"))
      (node (ref "X2") (pin "M1") (pinfunction "S1_M1") (pintype "passive"))
      (node (ref "X2") (pin "M2") (pinfunction "S2_M2") (pintype "passive"))
    )
    (net (code "62") (name "LED_1") (class "Default")
      (node (ref "MCU1") (pin "73") (pinfunction "PB12_73") (pintype "bidirectional"))
      (node (ref "R_LED1") (pin "2") (pinfunction "2_2") (pintype "passive"))
    )
    (net (code "63") (name "LED_2") (class "Default")
      (node (ref "MCU1") (pin "74") (pinfunction "PB13_74") (pintype "bidirectional"))
      (node (ref "R_LED2") (pin "2") (pinfunction "2_2") (pintype "passive"))
    )
    (net (code "64") (name "LED_3") (class "Default")
      (node (ref "MCU1") (pin "78") (pinfunction "PD9_78") (pintype "bidirectional"))
      (node (ref "R_LED3") (pin "2") (pinfunction "2_2") (pintype "passive"))
    )
    (net (code "65") (name "LED_4") (class "Default")
      (node (ref "MCU1") (pin "79") (pinfunction "PD10_79") (pintype "bidirectional"))
      (node (ref "R_LED4") (pin "2") (pinfunction "2_2") (pintype "passive"))
    )
    (net (code "66") (name "MCU_VCAP_1") (class "Default")
      (node (ref "MCU1") (pin "71") (pinfunction "VCAP_1_71") (pintype "bidirectional"))
      (node (ref "MCU_VCAP1") (pin "1") (pinfunction "1_1") (pintype "passive"))
    )
    (net (code "67") (name "MCU_VCAP_2") (class "Default")
      (node (ref "MCU1") (pin "106") (pinfunction "VCAP_2_106") (pintype "bidirectional"))
      (node (ref "MCU_VCAP2") (pin "1") (pinfunction "1_1") (pintype "passive"))
    )
    (net (code "68") (name "Net-(D_POWER-C)") (class "Default")
      (node (ref "C_VDD_3V3_3") (pin "1") (pinfunction "1_1") (pintype "passive"))
      (node (ref "D_POWER") (pin "K") (pinfunction "C_K") (pintype "passive"))
      (node (ref "D_USB") (pin "C") (pinfunction "OUT_C") (pintype "passive"))
      (node (ref "R_USB3") (pin "2") (pinfunction "2_2") (pintype "passive"))
      (node (ref "R_USB4") (pin "2") (pinfunction "2_2") (pintype "passive"))
      (node (ref "VREG1") (pin "1") (pinfunction "VI_1") (pintype "bidirectional"))
    )
    (net (code "69") (name "Net-(IC1-3V3OUT)") (class "Default")
      (node (ref "C_USB6") (pin "2") (pinfunction "2_2") (pintype "passive"))
      (node (ref "IC1") (pin "10") (pinfunction "3V3OUT_10") (pintype "output"))
      (node (ref "IC1") (pin "11") (pinfunction "~{RESET}_11") (pintype "input"))
      (node (ref "IC1") (pin "3") (pinfunction "VCCIO_3") (pintype "power_in"))
    )
    (net (code "70") (name "Net-(IC1-USBDM)") (class "Default")
      (node (ref "C_USB7") (pin "2") (pinfunction "2_2") (pintype "passive"))
      (node (ref "IC1") (pin "9") (pinfunction "USBDM_9") (pintype "input"))
      (node (ref "R_USB5") (pin "2") (pinfunction "2_2") (pintype "passive"))
    )
    (net (code "71") (name "Net-(IC1-USBDP)") (class "Default")
      (node (ref "C_USB8") (pin "2") (pinfunction "2_2") (pintype "passive"))
      (node (ref "IC1") (pin "8") (pinfunction "USBDP_8") (pintype "input"))
      (node (ref "R_USB6") (pin "2") (pinfunction "2_2") (pintype "passive"))
    )
    (net (code "72") (name "Net-(LED1-PadA)") (class "Default")
      (node (ref "LED1") (pin "A") (pinfunction "A_A") (pintype "passive"))
      (node (ref "R_LED1") (pin "1") (pinfunction "1_1") (pintype "passive"))
    )
    (net (code "73") (name "Net-(LED2-PadA)") (class "Default")
      (node (ref "LED2") (pin "A") (pinfunction "A_A") (pintype "passive"))
      (node (ref "R_LED2") (pin "1") (pinfunction "1_1") (pintype "passive"))
    )
    (net (code "74") (name "Net-(LED3-PadA)") (class "Default")
      (node (ref "LED3") (pin "A") (pinfunction "A_A") (pintype "passive"))
      (node (ref "R_LED3") (pin "1") (pinfunction "1_1") (pintype "passive"))
    )
    (net (code "75") (name "Net-(LED4-PadA)") (class "Default")
      (node (ref "LED4") (pin "A") (pinfunction "A_A") (pintype "passive"))
      (node (ref "R_LED4") (pin "1") (pinfunction "1_1") (pintype "passive"))
    )
    (net (code "76") (name "Net-(POWER-PadA)") (class "Default")
      (node (ref "POWER") (pin "A") (pinfunction "A_A") (pintype "passive"))
      (node (ref "R_USB3") (pin "1") (pinfunction "1_1") (pintype "passive"))
    )
    (net (code "77") (name "Net-(POWER1-PadA)") (class "Default")
      (node (ref "POWER1") (pin "A") (pinfunction "A_A") (pintype "passive"))
      (node (ref "R_USB4") (pin "1") (pinfunction "1_1") (pintype "passive"))
    )
    (net (code "78") (name "Net-(R_USB5-Pad1)") (class "Default")
      (node (ref "R_USB5") (pin "1") (pinfunction "1_1") (pintype "passive"))
      (node (ref "X2") (pin "2") (pinfunction "2_2") (pintype "passive"))
    )
    (net (code "79") (name "Net-(R_USB6-Pad1)") (class "Default")
      (node (ref "R_USB6") (pin "1") (pinfunction "1_1") (pintype "passive"))
      (node (ref "X2") (pin "3") (pinfunction "3_3") (pintype "passive"))
    )
    (net (code "80") (name "Net-(TLV6002A-+IN)") (class "Default")
      (node (ref "R_REF1") (pin "1") (pinfunction "1_1") (pintype "passive"))
      (node (ref "R_REF2") (pin "1") (pinfunction "1_1") (pintype "passive"))
      (node (ref "TLV6002") (pin "3") (pinfunction "+IN_3") (pintype "input"))
      (node (ref "V_REF") (pin "1") (pinfunction "C_1") (pintype "passive"))
    )
    (net (code "81") (name "UART4_RX") (class "Default")
      (node (ref "IC1") (pin "1") (pinfunction "TXD_1") (pintype "output"))
      (node (ref "MCU1") (pin "114") (pinfunction "PD0_114") (pintype "bidirectional"))
    )
    (net (code "82") (name "UART4_TX") (class "Default")
      (node (ref "IC1") (pin "4") (pinfunction "RXD_4") (pintype "input"))
      (node (ref "MCU1") (pin "115") (pinfunction "PD1_115") (pintype "bidirectional"))
    )
    (net (code "83") (name "VDD_3V3") (class "Default")
      (node (ref "C_USB10") (pin "2") (pinfunction "2_2") (pintype "passive"))
      (node (ref "C_USB9") (pin "2") (pinfunction "2_2") (pintype "passive"))
      (node (ref "C_VDD_3V3_1") (pin "1") (pinfunction "1_1") (pintype "passive"))
      (node (ref "C_VDD_3V3_2") (pin "1") (pinfunction "1_1") (pintype "passive"))
      (node (ref "IC1") (pin "12") (pinfunction "VCC_12") (pintype "power_in"))
      (node (ref "MCU1") (pin "108") (pinfunction "VDD_108") (pintype "bidirectional"))
      (node (ref "MCU1") (pin "121") (pinfunction "VDDSDMMC_121") (pintype "bidirectional"))
      (node (ref "MCU1") (pin "131") (pinfunction "VDD_131") (pintype "bidirectional"))
      (node (ref "MCU1") (pin "144") (pinfunction "VDD_144") (pintype "bidirectional"))
      (node (ref "MCU1") (pin "17") (pinfunction "VDD_17") (pintype "bidirectional"))
      (node (ref "MCU1") (pin "30") (pinfunction "VDD_30") (pintype "bidirectional"))
      (node (ref "MCU1") (pin "33") (pinfunction "VDDA_33") (pintype "bidirectional"))
      (node (ref "MCU1") (pin "39") (pinfunction "VDD_39") (pintype "bidirectional"))
      (node (ref "MCU1") (pin "52") (pinfunction "VDD_52") (pintype "bidirectional"))
      (node (ref "MCU1") (pin "6") (pinfunction "VBAT_6") (pintype "bidirectional"))
      (node (ref "MCU1") (pin "62") (pinfunction "VDD_62") (pintype "bidirectional"))
      (node (ref "MCU1") (pin "72") (pinfunction "VDD_72") (pintype "bidirectional"))
      (node (ref "MCU1") (pin "84") (pinfunction "VDD_84") (pintype "bidirectional"))
      (node (ref "MCU1") (pin "95") (pinfunction "VDDUSB_95") (pintype "bidirectional"))
      (node (ref "MCU_C1") (pin "1") (pinfunction "1_1") (pintype "passive"))
      (node (ref "MCU_C2") (pin "1") (pinfunction "1_1") (pintype "passive"))
      (node (ref "MCU_C3") (pin "1") (pinfunction "1_1") (pintype "passive"))
      (node (ref "MCU_C4") (pin "1") (pinfunction "1_1") (pintype "passive"))
      (node (ref "MCU_C5") (pin "1") (pinfunction "1_1") (pintype "passive"))
      (node (ref "MCU_C6") (pin "1") (pinfunction "1_1") (pintype "passive"))
      (node (ref "MCU_C7") (pin "1") (pinfunction "1_1") (pintype "passive"))
      (node (ref "MCU_USB_C") (pin "1") (pinfunction "1_1") (pintype "passive"))
      (node (ref "MCU_VDDA_C1") (pin "1") (pinfunction "1_1") (pintype "passive"))
      (node (ref "MCU_VDDA_C2") (pin "1") (pinfunction "1_1") (pintype "passive"))
      (node (ref "NRST_R") (pin "2") (pinfunction "2_2") (pintype "passive"))
      (node (ref "R_REF1") (pin "2") (pinfunction "2_2") (pintype "passive"))
      (node (ref "SWD") (pin "1") (pinfunction "1_1") (pintype "passive"))
      (node (ref "TLV6002") (pin "8") (pinfunction "V+_8") (pintype "power_in"))
      (node (ref "VREG1") (pin "3") (pinfunction "VO_3") (pintype "bidirectional"))
    )
    (net (code "84") (name "VDD_5V") (class "Default")
      (node (ref "CON1") (pin "49") (pinfunction "49_49") (pintype "passive"))
      (node (ref "D_POWER") (pin "A") (pinfunction "A_A") (pintype "passive"))
    )
    (net (code "85") (name "unconnected-(IC1-CBUS0-Pad15)") (class "Default")
      (node (ref "IC1") (pin "15") (pinfunction "CBUS0_15") (pintype "bidirectional"))
    )
    (net (code "86") (name "unconnected-(IC1-CBUS1-Pad14)") (class "Default")
      (node (ref "IC1") (pin "14") (pinfunction "CBUS1_14") (pintype "bidirectional"))
    )
    (net (code "87") (name "unconnected-(IC1-CBUS2-Pad7)") (class "Default")
      (node (ref "IC1") (pin "7") (pinfunction "CBUS2_7") (pintype "bidirectional"))
    )
    (net (code "88") (name "unconnected-(IC1-CBUS3-Pad16)") (class "Default")
      (node (ref "IC1") (pin "16") (pinfunction "CBUS3_16") (pintype "bidirectional"))
    )
    (net (code "89") (name "unconnected-(IC1-~{CTS}-Pad6)") (class "Default")
      (node (ref "IC1") (pin "6") (pinfunction "~{CTS}_6") (pintype "input"))
    )
    (net (code "90") (name "unconnected-(IC1-~{RTS}-Pad2)") (class "Default")
      (node (ref "IC1") (pin "2") (pinfunction "~{RTS}_2") (pintype "output"))
    )
    (net (code "91") (name "unconnected-(MCU1-BOOT0-Pad138)") (class "Default")
      (node (ref "MCU1") (pin "138") (pinfunction "BOOT0_138") (pintype "bidirectional"))
    )
    (net (code "92") (name "unconnected-(MCU1-PA2-Pad36)") (class "Default")
      (node (ref "MCU1") (pin "36") (pinfunction "PA2_36") (pintype "bidirectional"))
    )
    (net (code "93") (name "unconnected-(MCU1-PA6-Pad42)") (class "Default")
      (node (ref "MCU1") (pin "42") (pinfunction "PA6_42") (pintype "bidirectional"))
    )
    (net (code "94") (name "unconnected-(MCU1-PA8-Pad100)") (class "Default")
      (node (ref "MCU1") (pin "100") (pinfunction "PA8_100") (pintype "bidirectional"))
    )
    (net (code "95") (name "unconnected-(MCU1-PA9-Pad101)") (class "Default")
      (node (ref "MCU1") (pin "101") (pinfunction "PA9_101") (pintype "bidirectional"))
    )
    (net (code "96") (name "unconnected-(MCU1-PA10-Pad102)") (class "Default")
      (node (ref "MCU1") (pin "102") (pinfunction "PA10_102") (pintype "bidirectional"))
    )
    (net (code "97") (name "unconnected-(MCU1-PA11-Pad103)") (class "Default")
      (node (ref "MCU1") (pin "103") (pinfunction "PA11_103") (pintype "bidirectional"))
    )
    (net (code "98") (name "unconnected-(MCU1-PA12-Pad104)") (class "Default")
      (node (ref "MCU1") (pin "104") (pinfunction "PA12_104") (pintype "bidirectional"))
    )
    (net (code "99") (name "unconnected-(MCU1-PA15-Pad110)") (class "Default")
      (node (ref "MCU1") (pin "110") (pinfunction "PA15_110") (pintype "bidirectional"))
    )
    (net (code "100") (name "unconnected-(MCU1-PB2-Pad48)") (class "Default")
      (node (ref "MCU1") (pin "48") (pinfunction "PB2_48") (pintype "bidirectional"))
    )
    (net (code "101") (name "unconnected-(MCU1-PB5-Pad135)") (class "Default")
      (node (ref "MCU1") (pin "135") (pinfunction "PB5_135") (pintype "bidirectional"))
    )
    (net (code "102") (name "unconnected-(MCU1-PB6-Pad136)") (class "Default")
      (node (ref "MCU1") (pin "136") (pinfunction "PB6_136") (pintype "bidirectional"))
    )
    (net (code "103") (name "unconnected-(MCU1-PB7-Pad137)") (class "Default")
      (node (ref "MCU1") (pin "137") (pinfunction "PB7_137") (pintype "bidirectional"))
    )
    (net (code "104") (name "unconnected-(MCU1-PB8-Pad139)") (class "Default")
      (node (ref "MCU1") (pin "139") (pinfunction "PB8_139") (pintype "bidirectional"))
    )
    (net (code "105") (name "unconnected-(MCU1-PB9-Pad140)") (class "Default")
      (node (ref "MCU1") (pin "140") (pinfunction "PB9_140") (pintype "bidirectional"))
    )
    (net (code "106") (name "unconnected-(MCU1-PB10-Pad69)") (class "Default")
      (node (ref "MCU1") (pin "69") (pinfunction "PB10_69") (pintype "bidirectional"))
    )
    (net (code "107") (name "unconnected-(MCU1-PB11-Pad70)") (class "Default")
      (node (ref "MCU1") (pin "70") (pinfunction "PB11_70") (pintype "bidirectional"))
    )
    (net (code "108") (name "unconnected-(MCU1-PC9-Pad99)") (class "Default")
      (node (ref "MCU1") (pin "99") (pinfunction "PC9_99") (pintype "bidirectional"))
    )
    (net (code "109") (name "unconnected-(MCU1-PC13-Pad7)") (class "Default")
      (node (ref "MCU1") (pin "7") (pinfunction "PC13_7") (pintype "bidirectional"))
    )
    (net (code "110") (name "unconnected-(MCU1-PC14-Pad8)") (class "Default")
      (node (ref "MCU1") (pin "8") (pinfunction "PC14_8") (pintype "bidirectional"))
    )
    (net (code "111") (name "unconnected-(MCU1-PC15-Pad9)") (class "Default")
      (node (ref "MCU1") (pin "9") (pinfunction "PC15_9") (pintype "bidirectional"))
    )
    (net (code "112") (name "unconnected-(MCU1-PD2-Pad116)") (class "Default")
      (node (ref "MCU1") (pin "116") (pinfunction "PD2_116") (pintype "bidirectional"))
    )
    (net (code "113") (name "unconnected-(MCU1-PD3-Pad117)") (class "Default")
      (node (ref "MCU1") (pin "117") (pinfunction "PD3_117") (pintype "bidirectional"))
    )
    (net (code "114") (name "unconnected-(MCU1-PD4-Pad118)") (class "Default")
      (node (ref "MCU1") (pin "118") (pinfunction "PD4_118") (pintype "bidirectional"))
    )
    (net (code "115") (name "unconnected-(MCU1-PD5-Pad119)") (class "Default")
      (node (ref "MCU1") (pin "119") (pinfunction "PD5_119") (pintype "bidirectional"))
    )
    (net (code "116") (name "unconnected-(MCU1-PD8-Pad77)") (class "Default")
      (node (ref "MCU1") (pin "77") (pinfunction "PD8_77") (pintype "bidirectional"))
    )
    (net (code "117") (name "unconnected-(MCU1-PD11-Pad80)") (class "Default")
      (node (ref "MCU1") (pin "80") (pinfunction "PD11_80") (pintype "bidirectional"))
    )
    (net (code "118") (name "unconnected-(MCU1-PD14-Pad85)") (class "Default")
      (node (ref "MCU1") (pin "85") (pinfunction "PD14_85") (pintype "bidirectional"))
    )
    (net (code "119") (name "unconnected-(MCU1-PD15-Pad86)") (class "Default")
      (node (ref "MCU1") (pin "86") (pinfunction "PD15_86") (pintype "bidirectional"))
    )
    (net (code "120") (name "unconnected-(MCU1-PE0-Pad141)") (class "Default")
      (node (ref "MCU1") (pin "141") (pinfunction "PE0_141") (pintype "bidirectional"))
    )
    (net (code "121") (name "unconnected-(MCU1-PE1-Pad142)") (class "Default")
      (node (ref "MCU1") (pin "142") (pinfunction "PE1_142") (pintype "bidirectional"))
    )
    (net (code "122") (name "unconnected-(MCU1-PE2-Pad1)") (class "Default")
      (node (ref "MCU1") (pin "1") (pinfunction "PE2_1") (pintype "bidirectional"))
    )
    (net (code "123") (name "unconnected-(MCU1-PE3-Pad2)") (class "Default")
      (node (ref "MCU1") (pin "2") (pinfunction "PE3_2") (pintype "bidirectional"))
    )
    (net (code "124") (name "unconnected-(MCU1-PE4-Pad3)") (class "Default")
      (node (ref "MCU1") (pin "3") (pinfunction "PE4_3") (pintype "bidirectional"))
    )
    (net (code "125") (name "unconnected-(MCU1-PE5-Pad4)") (class "Default")
      (node (ref "MCU1") (pin "4") (pinfunction "PE5_4") (pintype "bidirectional"))
    )
    (net (code "126") (name "unconnected-(MCU1-PE6-Pad5)") (class "Default")
      (node (ref "MCU1") (pin "5") (pinfunction "PE6_5") (pintype "bidirectional"))
    )
    (net (code "127") (name "unconnected-(MCU1-PE7-Pad58)") (class "Default")
      (node (ref "MCU1") (pin "58") (pinfunction "PE7_58") (pintype "bidirectional"))
    )
    (net (code "128") (name "unconnected-(MCU1-PE14-Pad67)") (class "Default")
      (node (ref "MCU1") (pin "67") (pinfunction "PE14_67") (pintype "bidirectional"))
    )
    (net (code "129") (name "unconnected-(MCU1-PF0-Pad10)") (class "Default")
      (node (ref "MCU1") (pin "10") (pinfunction "PF0_10") (pintype "bidirectional"))
    )
    (net (code "130") (name "unconnected-(MCU1-PF1-Pad11)") (class "Default")
      (node (ref "MCU1") (pin "11") (pinfunction "PF1_11") (pintype "bidirectional"))
    )
    (net (code "131") (name "unconnected-(MCU1-PF2-Pad12)") (class "Default")
      (node (ref "MCU1") (pin "12") (pinfunction "PF2_12") (pintype "bidirectional"))
    )
    (net (code "132") (name "unconnected-(MCU1-PG0-Pad56)") (class "Default")
      (node (ref "MCU1") (pin "56") (pinfunction "PG0_56") (pintype "bidirectional"))
    )
    (net (code "133") (name "unconnected-(MCU1-PG1-Pad57)") (class "Default")
      (node (ref "MCU1") (pin "57") (pinfunction "PG1_57") (pintype "bidirectional"))
    )
    (net (code "134") (name "unconnected-(MCU1-PG5-Pad90)") (class "Default")
      (node (ref "MCU1") (pin "90") (pinfunction "PG5_90") (pintype "bidirectional"))
    )
    (net (code "135") (name "unconnected-(MCU1-PG6-Pad91)") (class "Default")
      (node (ref "MCU1") (pin "91") (pinfunction "PG6_91") (pintype "bidirectional"))
    )
    (net (code "136") (name "unconnected-(MCU1-PG7-Pad92)") (class "Default")
      (node (ref "MCU1") (pin "92") (pinfunction "PG7_92") (pintype "bidirectional"))
    )
    (net (code "137") (name "unconnected-(MCU1-PG8-Pad93)") (class "Default")
      (node (ref "MCU1") (pin "93") (pinfunction "PG8_93") (pintype "bidirectional"))
    )
    (net (code "138") (name "unconnected-(MCU1-PG9-Pad124)") (class "Default")
      (node (ref "MCU1") (pin "124") (pinfunction "PG9_124") (pintype "bidirectional"))
    )
    (net (code "139") (name "unconnected-(MCU1-PG10-Pad125)") (class "Default")
      (node (ref "MCU1") (pin "125") (pinfunction "PG10_125") (pintype "bidirectional"))
    )
    (net (code "140") (name "unconnected-(MCU1-PG15-Pad132)") (class "Default")
      (node (ref "MCU1") (pin "132") (pinfunction "PG15_132") (pintype "bidirectional"))
    )
    (net (code "141") (name "unconnected-(MCU1-PH0-Pad23)") (class "Default")
      (node (ref "MCU1") (pin "23") (pinfunction "PH0_23") (pintype "bidirectional"))
    )
    (net (code "142") (name "unconnected-(MCU1-PH1-Pad24)") (class "Default")
      (node (ref "MCU1") (pin "24") (pinfunction "PH1_24") (pintype "bidirectional"))
    )
  )
)
